# Eitech-Robotics_v10.net
KiCad netlist of a schematic drawn in EAGLE
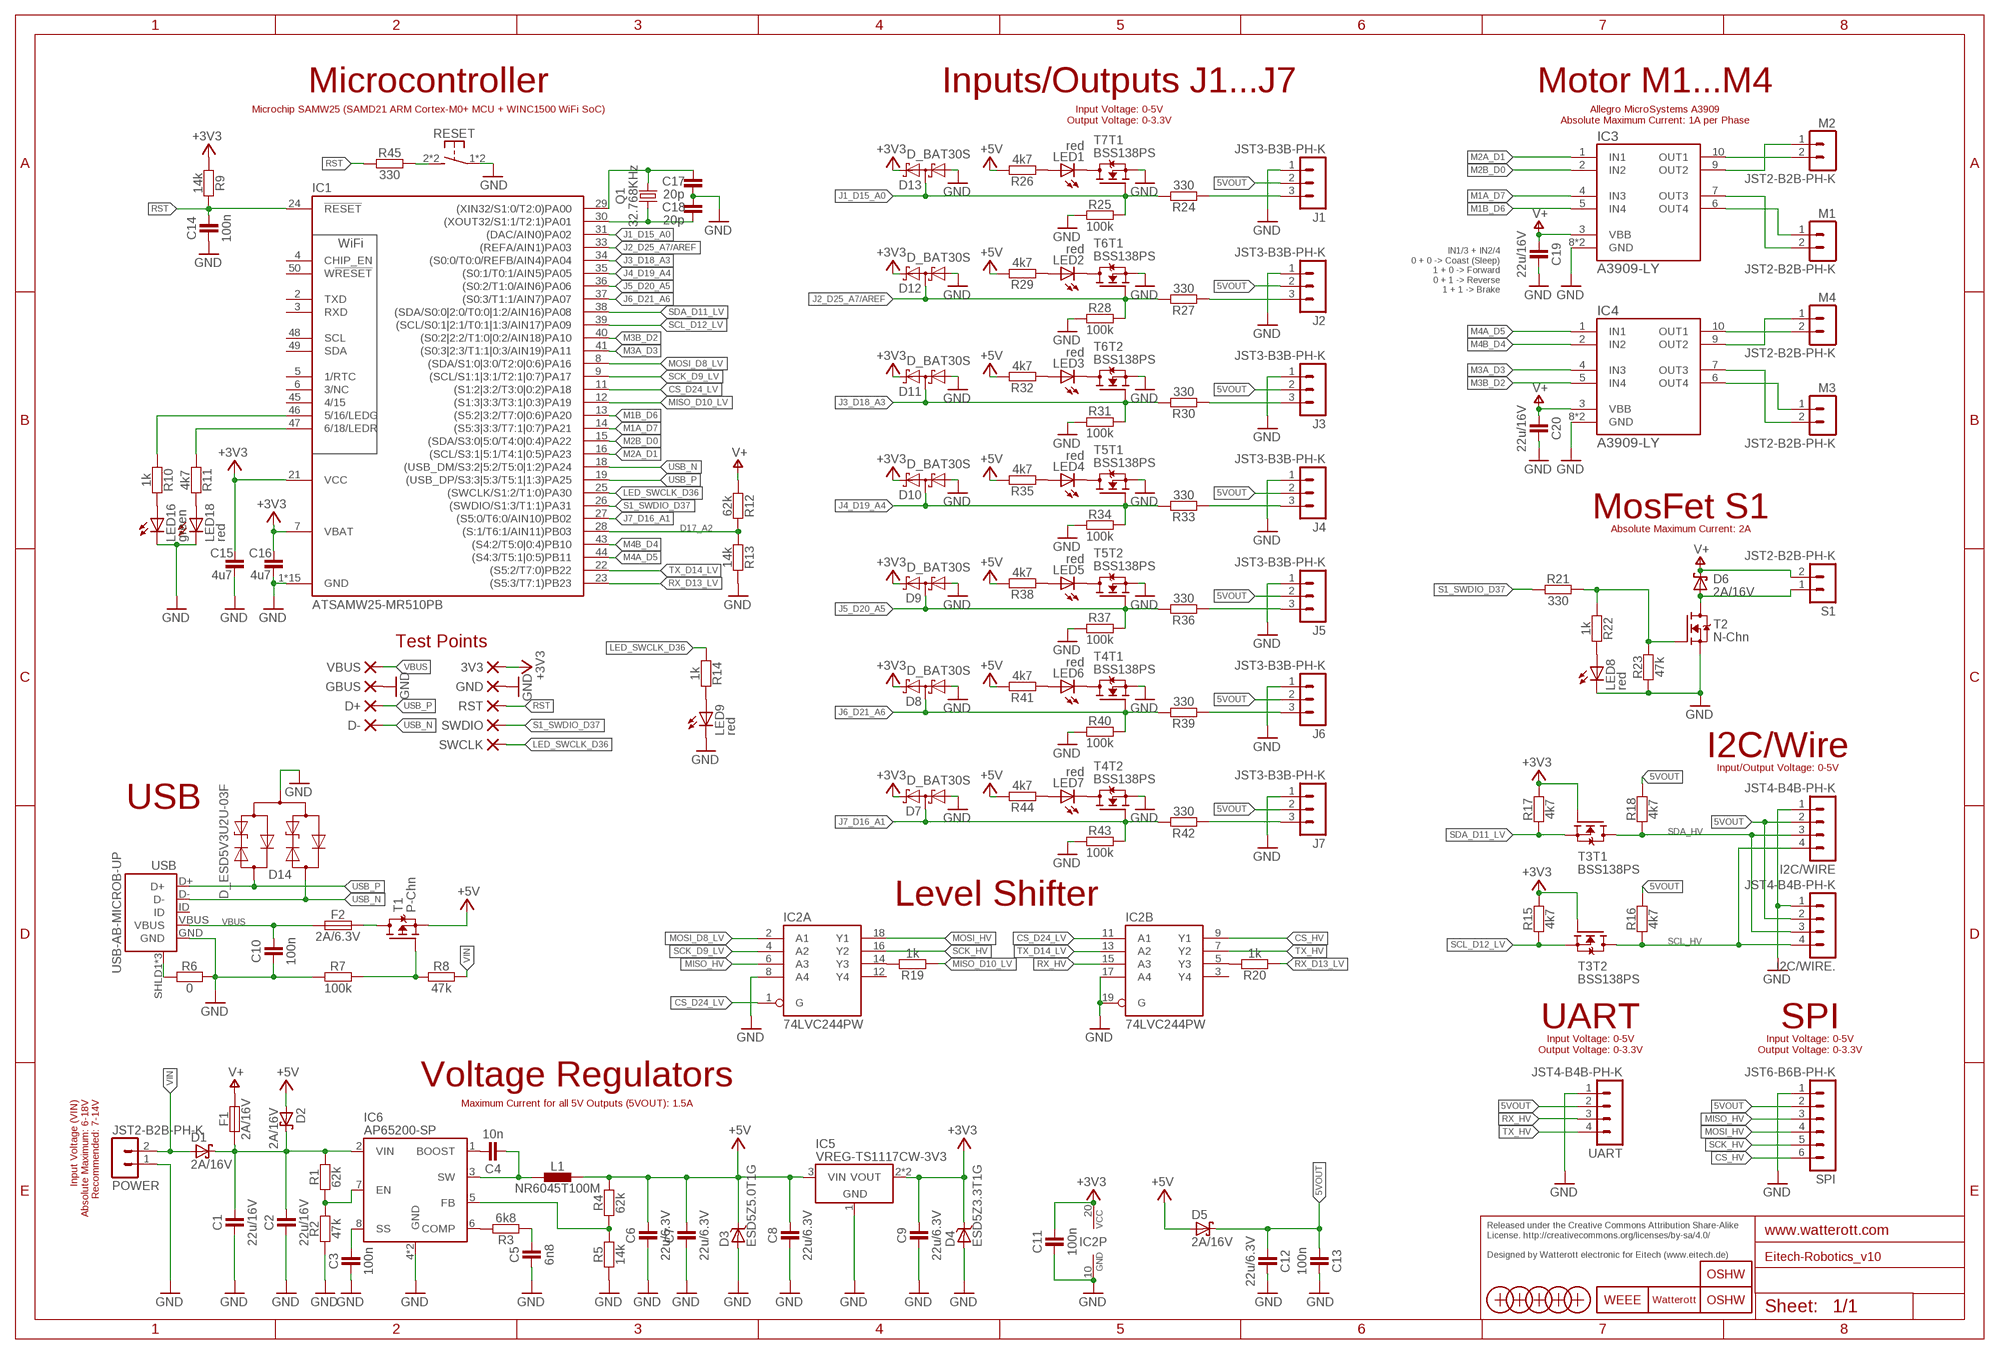
[diagram p0: schematic, sheet 1]

(export (version "E")
  (design (tool "Eeschema 10.0.6"))
  (components
    (comp (ref "3V3")
      (value "PAD-1.0_NC")
      (footprint "eagle-import:PAD-1.0_NC")
      (libsource (lib "eagle-import") (part "PAD-1.0_NC"))
    )
    (comp (ref "C1")
      (value "22u/16V")
      (footprint "eagle-import:C0805")
      (libsource (lib "eagle-import") (part "CAPACITOR-0805"))
    )
    (comp (ref "C2")
      (value "22u/16V")
      (footprint "eagle-import:C0805")
      (libsource (lib "eagle-import") (part "CAPACITOR-0805"))
    )
    (comp (ref "C3")
      (value "100n")
      (footprint "eagle-import:C0402")
      (libsource (lib "eagle-import") (part "CAPACITOR-0402"))
    )
    (comp (ref "C4")
      (value "10n")
      (footprint "eagle-import:C0402")
      (libsource (lib "eagle-import") (part "CAPACITOR-0402"))
    )
    (comp (ref "C5")
      (value "6n8")
      (footprint "eagle-import:C0402")
      (libsource (lib "eagle-import") (part "CAPACITOR-0402"))
    )
    (comp (ref "C6")
      (value "22u/6.3V")
      (footprint "eagle-import:C0805")
      (libsource (lib "eagle-import") (part "CAPACITOR-0805"))
    )
    (comp (ref "C7")
      (value "22u/6.3V")
      (footprint "eagle-import:C0805")
      (libsource (lib "eagle-import") (part "CAPACITOR-0805"))
    )
    (comp (ref "C8")
      (value "22u/6.3V")
      (footprint "eagle-import:C0805")
      (libsource (lib "eagle-import") (part "CAPACITOR-0805"))
    )
    (comp (ref "C9")
      (value "22u/6.3V")
      (footprint "eagle-import:C0805")
      (libsource (lib "eagle-import") (part "CAPACITOR-0805"))
    )
    (comp (ref "C10")
      (value "100n")
      (footprint "eagle-import:C0402")
      (libsource (lib "eagle-import") (part "CAPACITOR-0402"))
    )
    (comp (ref "C11")
      (value "100n")
      (footprint "eagle-import:C0402")
      (libsource (lib "eagle-import") (part "CAPACITOR-0402"))
    )
    (comp (ref "C12")
      (value "22u/6.3V")
      (footprint "eagle-import:C0805")
      (libsource (lib "eagle-import") (part "CAPACITOR-0805"))
    )
    (comp (ref "C13")
      (value "100n")
      (footprint "eagle-import:C0402")
      (libsource (lib "eagle-import") (part "CAPACITOR-0402"))
    )
    (comp (ref "C14")
      (value "100n")
      (footprint "eagle-import:C0402")
      (libsource (lib "eagle-import") (part "CAPACITOR-0402"))
    )
    (comp (ref "C15")
      (value "4u7")
      (footprint "eagle-import:C0603")
      (libsource (lib "eagle-import") (part "CAPACITOR-0603"))
    )
    (comp (ref "C16")
      (value "4u7")
      (footprint "eagle-import:C0603")
      (libsource (lib "eagle-import") (part "CAPACITOR-0603"))
    )
    (comp (ref "C17")
      (value "20p")
      (footprint "eagle-import:C0402")
      (libsource (lib "eagle-import") (part "CAPACITOR-0402"))
    )
    (comp (ref "C18")
      (value "20p")
      (footprint "eagle-import:C0402")
      (libsource (lib "eagle-import") (part "CAPACITOR-0402"))
    )
    (comp (ref "C19")
      (value "22u/16V")
      (footprint "eagle-import:C0805")
      (libsource (lib "eagle-import") (part "CAPACITOR-0805"))
    )
    (comp (ref "C20")
      (value "22u/16V")
      (footprint "eagle-import:C0805")
      (libsource (lib "eagle-import") (part "CAPACITOR-0805"))
    )
    (comp (ref "D+")
      (value "PAD-1.0_NC")
      (footprint "eagle-import:PAD-1.0_NC")
      (libsource (lib "eagle-import") (part "PAD-1.0_NC"))
    )
    (comp (ref "D-")
      (value "PAD-1.0_NC")
      (footprint "eagle-import:PAD-1.0_NC")
      (libsource (lib "eagle-import") (part "PAD-1.0_NC"))
    )
    (comp (ref "D1")
      (value "2A/16V")
      (footprint "eagle-import:SMA_DO214AC")
      (libsource (lib "eagle-import") (part "D_SCHOTTKY-SMA"))
    )
    (comp (ref "D2")
      (value "2A/16V")
      (footprint "eagle-import:SMA_DO214AC")
      (libsource (lib "eagle-import") (part "D_SCHOTTKY-SMA"))
    )
    (comp (ref "D3")
      (value "ESD5Z5.0T1G")
      (footprint "eagle-import:SOD523")
      (libsource (lib "eagle-import") (part "D_TVS-SOD523"))
    )
    (comp (ref "D4")
      (value "ESD5Z3.3T1G")
      (footprint "eagle-import:SOD523")
      (libsource (lib "eagle-import") (part "D_TVS-SOD523"))
    )
    (comp (ref "D5")
      (value "2A/16V")
      (footprint "eagle-import:SMA_DO214AC")
      (libsource (lib "eagle-import") (part "D_SCHOTTKY-SMA"))
    )
    (comp (ref "D6")
      (value "2A/16V")
      (footprint "eagle-import:SMA_DO214AC")
      (libsource (lib "eagle-import") (part "D_SCHOTTKY-SMA"))
    )
    (comp (ref "D7")
      (value "D_BAT30S")
      (footprint "eagle-import:SOT323")
      (libsource (lib "eagle-import") (part "D_BAT30S"))
    )
    (comp (ref "D8")
      (value "D_BAT30S")
      (footprint "eagle-import:SOT323")
      (libsource (lib "eagle-import") (part "D_BAT30S"))
    )
    (comp (ref "D9")
      (value "D_BAT30S")
      (footprint "eagle-import:SOT323")
      (libsource (lib "eagle-import") (part "D_BAT30S"))
    )
    (comp (ref "D10")
      (value "D_BAT30S")
      (footprint "eagle-import:SOT323")
      (libsource (lib "eagle-import") (part "D_BAT30S"))
    )
    (comp (ref "D11")
      (value "D_BAT30S")
      (footprint "eagle-import:SOT323")
      (libsource (lib "eagle-import") (part "D_BAT30S"))
    )
    (comp (ref "D12")
      (value "D_BAT30S")
      (footprint "eagle-import:SOT323")
      (libsource (lib "eagle-import") (part "D_BAT30S"))
    )
    (comp (ref "D13")
      (value "D_BAT30S")
      (footprint "eagle-import:SOT323")
      (libsource (lib "eagle-import") (part "D_BAT30S"))
    )
    (comp (ref "D14")
      (value "D_ESD5V3U2U-03F")
      (footprint "eagle-import:SOT723")
      (libsource (lib "eagle-import") (part "D_ESD5V3U2U-03F"))
    )
    (comp (ref "F1")
      (value "2A/16V")
      (footprint "eagle-import:C1812")
      (libsource (lib "eagle-import") (part "FUSE-1812"))
    )
    (comp (ref "F2")
      (value "2A/6.3V")
      (footprint "eagle-import:C1206")
      (libsource (lib "eagle-import") (part "FUSE-1206"))
    )
    (comp (ref "GBUS")
      (value "PAD-1.0_NC")
      (footprint "eagle-import:PAD-1.0_NC")
      (libsource (lib "eagle-import") (part "PAD-1.0_NC"))
    )
    (comp (ref "GND")
      (value "PAD-1.0_NC")
      (footprint "eagle-import:PAD-1.0_NC")
      (libsource (lib "eagle-import") (part "PAD-1.0_NC"))
    )
    (comp (ref "I2C/WIRE")
      (value "JST4-B4B-PH-K")
      (footprint "eagle-import:JST_B4B-PH-K")
      (libsource (lib "eagle-import") (part "JST4-B4B-PH-K"))
    )
    (comp (ref "I2C/WIRE.")
      (value "JST4-B4B-PH-K")
      (footprint "eagle-import:JST_B4B-PH-K")
      (libsource (lib "eagle-import") (part "JST4-B4B-PH-K"))
    )
    (comp (ref "IC1")
      (value "ATSAMW25-MR510PB")
      (footprint "eagle-import:ATSAMW25-MRX10")
      (libsource (lib "eagle-import") (part "ATSAMW25-MR510PB"))
    )
    (comp (ref "IC2")
      (value "74LVC244PW")
      (footprint "eagle-import:TSSOP20")
      (libsource (lib "eagle-import") (part "74244PWLVC"))
    )
    (comp (ref "IC3")
      (value "A3909-LY")
      (footprint "eagle-import:MSOP10-PAD")
      (libsource (lib "eagle-import") (part "A3909-LY"))
    )
    (comp (ref "IC4")
      (value "A3909-LY")
      (footprint "eagle-import:MSOP10-PAD")
      (libsource (lib "eagle-import") (part "A3909-LY"))
    )
    (comp (ref "IC5")
      (value "VREG-TS1117CW-3V3")
      (footprint "eagle-import:SOT223")
      (libsource (lib "eagle-import") (part "VREG-TS1117CW-3V3"))
    )
    (comp (ref "IC6")
      (value "AP65200-SP")
      (footprint "eagle-import:SO08-PAD")
      (libsource (lib "eagle-import") (part "AP65200-SP"))
    )
    (comp (ref "J1")
      (value "JST3-B3B-PH-K")
      (footprint "eagle-import:JST_B3B-PH-K")
      (libsource (lib "eagle-import") (part "JST3-B3B-PH-K"))
    )
    (comp (ref "J2")
      (value "JST3-B3B-PH-K")
      (footprint "eagle-import:JST_B3B-PH-K")
      (libsource (lib "eagle-import") (part "JST3-B3B-PH-K"))
    )
    (comp (ref "J3")
      (value "JST3-B3B-PH-K")
      (footprint "eagle-import:JST_B3B-PH-K")
      (libsource (lib "eagle-import") (part "JST3-B3B-PH-K"))
    )
    (comp (ref "J4")
      (value "JST3-B3B-PH-K")
      (footprint "eagle-import:JST_B3B-PH-K")
      (libsource (lib "eagle-import") (part "JST3-B3B-PH-K"))
    )
    (comp (ref "J5")
      (value "JST3-B3B-PH-K")
      (footprint "eagle-import:JST_B3B-PH-K")
      (libsource (lib "eagle-import") (part "JST3-B3B-PH-K"))
    )
    (comp (ref "J6")
      (value "JST3-B3B-PH-K")
      (footprint "eagle-import:JST_B3B-PH-K")
      (libsource (lib "eagle-import") (part "JST3-B3B-PH-K"))
    )
    (comp (ref "J7")
      (value "JST3-B3B-PH-K")
      (footprint "eagle-import:JST_B3B-PH-K")
      (libsource (lib "eagle-import") (part "JST3-B3B-PH-K"))
    )
    (comp (ref "L1")
      (value "NR6045T100M")
      (footprint "eagle-import:L_NR60XX")
      (libsource (lib "eagle-import") (part "INDUCTOR-NR60XX"))
    )
    (comp (ref "LED1")
      (value "red")
      (footprint "eagle-import:C0603")
      (libsource (lib "eagle-import") (part "LED-0603"))
    )
    (comp (ref "LED2")
      (value "red")
      (footprint "eagle-import:C0603")
      (libsource (lib "eagle-import") (part "LED-0603"))
    )
    (comp (ref "LED3")
      (value "red")
      (footprint "eagle-import:C0603")
      (libsource (lib "eagle-import") (part "LED-0603"))
    )
    (comp (ref "LED4")
      (value "red")
      (footprint "eagle-import:C0603")
      (libsource (lib "eagle-import") (part "LED-0603"))
    )
    (comp (ref "LED5")
      (value "red")
      (footprint "eagle-import:C0603")
      (libsource (lib "eagle-import") (part "LED-0603"))
    )
    (comp (ref "LED6")
      (value "red")
      (footprint "eagle-import:C0603")
      (libsource (lib "eagle-import") (part "LED-0603"))
    )
    (comp (ref "LED7")
      (value "red")
      (footprint "eagle-import:C0603")
      (libsource (lib "eagle-import") (part "LED-0603"))
    )
    (comp (ref "LED8")
      (value "red")
      (footprint "eagle-import:C0603")
      (libsource (lib "eagle-import") (part "LED-0603"))
    )
    (comp (ref "LED9")
      (value "red")
      (footprint "eagle-import:C0603")
      (libsource (lib "eagle-import") (part "LED-0603"))
    )
    (comp (ref "LED16")
      (value "green")
      (footprint "eagle-import:C0603")
      (libsource (lib "eagle-import") (part "LED-0603"))
    )
    (comp (ref "LED18")
      (value "red")
      (footprint "eagle-import:C0603")
      (libsource (lib "eagle-import") (part "LED-0603"))
    )
    (comp (ref "LOGO1")
      (value "OSHW_LOGOX0100")
      (footprint "eagle-import:OSHW_6X100")
      (libsource (lib "eagle-import") (part "OSHW_LOGOX0100"))
    )
    (comp (ref "LOGO2")
      (value "OSHW_LOGOX0150")
      (footprint "eagle-import:OSHW_6X150")
      (libsource (lib "eagle-import") (part "OSHW_LOGOX0150"))
    )
    (comp (ref "LOGO3")
      (value "LOGO-S_PLACE_S")
      (footprint "eagle-import:SPARK_TPLACE_S")
      (libsource (lib "eagle-import") (part "LOGO-S_PLACE_S"))
    )
    (comp (ref "LOGO4")
      (value "WEEE_LOGO-S")
      (footprint "eagle-import:WEEE_TPLAC_S")
      (libsource (lib "eagle-import") (part "WEEE_LOGO-S"))
    )
    (comp (ref "M1")
      (value "JST2-B2B-PH-K")
      (footprint "eagle-import:JST_B2B-PH-K")
      (libsource (lib "eagle-import") (part "JST2-B2B-PH-K"))
    )
    (comp (ref "M2")
      (value "JST2-B2B-PH-K")
      (footprint "eagle-import:JST_B2B-PH-K")
      (libsource (lib "eagle-import") (part "JST2-B2B-PH-K"))
    )
    (comp (ref "M3")
      (value "JST2-B2B-PH-K")
      (footprint "eagle-import:JST_B2B-PH-K")
      (libsource (lib "eagle-import") (part "JST2-B2B-PH-K"))
    )
    (comp (ref "M4")
      (value "JST2-B2B-PH-K")
      (footprint "eagle-import:JST_B2B-PH-K")
      (libsource (lib "eagle-import") (part "JST2-B2B-PH-K"))
    )
    (comp (ref "POWER")
      (value "JST2-B2B-PH-K")
      (footprint "eagle-import:JST_B2B-PH-K")
      (libsource (lib "eagle-import") (part "JST2-B2B-PH-K"))
    )
    (comp (ref "Q1")
      (value "32.768KHz")
      (footprint "eagle-import:CRYSTAL_ZM315")
      (libsource (lib "eagle-import") (part "CRYSTAL-ZM315"))
    )
    (comp (ref "R1")
      (value "62k")
      (footprint "eagle-import:C0402")
      (libsource (lib "eagle-import") (part "RESISTOR-0402"))
    )
    (comp (ref "R2")
      (value "47k")
      (footprint "eagle-import:C0402")
      (libsource (lib "eagle-import") (part "RESISTOR-0402"))
    )
    (comp (ref "R3")
      (value "6k8")
      (footprint "eagle-import:C0402")
      (libsource (lib "eagle-import") (part "RESISTOR-0402"))
    )
    (comp (ref "R4")
      (value "62k")
      (footprint "eagle-import:C0402")
      (libsource (lib "eagle-import") (part "RESISTOR-0402"))
    )
    (comp (ref "R5")
      (value "14k")
      (footprint "eagle-import:C0402")
      (libsource (lib "eagle-import") (part "RESISTOR-0402"))
    )
    (comp (ref "R6")
      (value "0")
      (footprint "eagle-import:C0402")
      (libsource (lib "eagle-import") (part "RESISTOR-0402"))
    )
    (comp (ref "R7")
      (value "100k")
      (footprint "eagle-import:C0402")
      (libsource (lib "eagle-import") (part "RESISTOR-0402"))
    )
    (comp (ref "R8")
      (value "47k")
      (footprint "eagle-import:C0402")
      (libsource (lib "eagle-import") (part "RESISTOR-0402"))
    )
    (comp (ref "R9")
      (value "14k")
      (footprint "eagle-import:C0402")
      (libsource (lib "eagle-import") (part "RESISTOR-0402"))
    )
    (comp (ref "R10")
      (value "1k")
      (footprint "eagle-import:C0402")
      (libsource (lib "eagle-import") (part "RESISTOR-0402"))
    )
    (comp (ref "R11")
      (value "4k7")
      (footprint "eagle-import:C0402")
      (libsource (lib "eagle-import") (part "RESISTOR-0402"))
    )
    (comp (ref "R12")
      (value "62k")
      (footprint "eagle-import:C0402")
      (libsource (lib "eagle-import") (part "RESISTOR-0402"))
    )
    (comp (ref "R13")
      (value "14k")
      (footprint "eagle-import:C0402")
      (libsource (lib "eagle-import") (part "RESISTOR-0402"))
    )
    (comp (ref "R14")
      (value "1k")
      (footprint "eagle-import:C0402")
      (libsource (lib "eagle-import") (part "RESISTOR-0402"))
    )
    (comp (ref "R15")
      (value "4k7")
      (footprint "eagle-import:C0402")
      (libsource (lib "eagle-import") (part "RESISTOR-0402"))
    )
    (comp (ref "R16")
      (value "4k7")
      (footprint "eagle-import:C0402")
      (libsource (lib "eagle-import") (part "RESISTOR-0402"))
    )
    (comp (ref "R17")
      (value "4k7")
      (footprint "eagle-import:C0402")
      (libsource (lib "eagle-import") (part "RESISTOR-0402"))
    )
    (comp (ref "R18")
      (value "4k7")
      (footprint "eagle-import:C0402")
      (libsource (lib "eagle-import") (part "RESISTOR-0402"))
    )
    (comp (ref "R19")
      (value "1k")
      (footprint "eagle-import:C0402")
      (libsource (lib "eagle-import") (part "RESISTOR-0402"))
    )
    (comp (ref "R20")
      (value "1k")
      (footprint "eagle-import:C0402")
      (libsource (lib "eagle-import") (part "RESISTOR-0402"))
    )
    (comp (ref "R21")
      (value "330")
      (footprint "eagle-import:C0402")
      (libsource (lib "eagle-import") (part "RESISTOR-0402"))
    )
    (comp (ref "R22")
      (value "1k")
      (footprint "eagle-import:C0402")
      (libsource (lib "eagle-import") (part "RESISTOR-0402"))
    )
    (comp (ref "R23")
      (value "47k")
      (footprint "eagle-import:C0402")
      (libsource (lib "eagle-import") (part "RESISTOR-0402"))
    )
    (comp (ref "R24")
      (value "330")
      (footprint "eagle-import:C0402")
      (libsource (lib "eagle-import") (part "RESISTOR-0402"))
    )
    (comp (ref "R25")
      (value "100k")
      (footprint "eagle-import:C0402")
      (libsource (lib "eagle-import") (part "RESISTOR-0402"))
    )
    (comp (ref "R26")
      (value "4k7")
      (footprint "eagle-import:C0402")
      (libsource (lib "eagle-import") (part "RESISTOR-0402"))
    )
    (comp (ref "R27")
      (value "330")
      (footprint "eagle-import:C0402")
      (libsource (lib "eagle-import") (part "RESISTOR-0402"))
    )
    (comp (ref "R28")
      (value "100k")
      (footprint "eagle-import:C0402")
      (libsource (lib "eagle-import") (part "RESISTOR-0402"))
    )
    (comp (ref "R29")
      (value "4k7")
      (footprint "eagle-import:C0402")
      (libsource (lib "eagle-import") (part "RESISTOR-0402"))
    )
    (comp (ref "R30")
      (value "330")
      (footprint "eagle-import:C0402")
      (libsource (lib "eagle-import") (part "RESISTOR-0402"))
    )
    (comp (ref "R31")
      (value "100k")
      (footprint "eagle-import:C0402")
      (libsource (lib "eagle-import") (part "RESISTOR-0402"))
    )
    (comp (ref "R32")
      (value "4k7")
      (footprint "eagle-import:C0402")
      (libsource (lib "eagle-import") (part "RESISTOR-0402"))
    )
    (comp (ref "R33")
      (value "330")
      (footprint "eagle-import:C0402")
      (libsource (lib "eagle-import") (part "RESISTOR-0402"))
    )
    (comp (ref "R34")
      (value "100k")
      (footprint "eagle-import:C0402")
      (libsource (lib "eagle-import") (part "RESISTOR-0402"))
    )
    (comp (ref "R35")
      (value "4k7")
      (footprint "eagle-import:C0402")
      (libsource (lib "eagle-import") (part "RESISTOR-0402"))
    )
    (comp (ref "R36")
      (value "330")
      (footprint "eagle-import:C0402")
      (libsource (lib "eagle-import") (part "RESISTOR-0402"))
    )
    (comp (ref "R37")
      (value "100k")
      (footprint "eagle-import:C0402")
      (libsource (lib "eagle-import") (part "RESISTOR-0402"))
    )
    (comp (ref "R38")
      (value "4k7")
      (footprint "eagle-import:C0402")
      (libsource (lib "eagle-import") (part "RESISTOR-0402"))
    )
    (comp (ref "R39")
      (value "330")
      (footprint "eagle-import:C0402")
      (libsource (lib "eagle-import") (part "RESISTOR-0402"))
    )
    (comp (ref "R40")
      (value "100k")
      (footprint "eagle-import:C0402")
      (libsource (lib "eagle-import") (part "RESISTOR-0402"))
    )
    (comp (ref "R41")
      (value "4k7")
      (footprint "eagle-import:C0402")
      (libsource (lib "eagle-import") (part "RESISTOR-0402"))
    )
    (comp (ref "R42")
      (value "330")
      (footprint "eagle-import:C0402")
      (libsource (lib "eagle-import") (part "RESISTOR-0402"))
    )
    (comp (ref "R43")
      (value "100k")
      (footprint "eagle-import:C0402")
      (libsource (lib "eagle-import") (part "RESISTOR-0402"))
    )
    (comp (ref "R44")
      (value "4k7")
      (footprint "eagle-import:C0402")
      (libsource (lib "eagle-import") (part "RESISTOR-0402"))
    )
    (comp (ref "R45")
      (value "330")
      (footprint "eagle-import:C0402")
      (libsource (lib "eagle-import") (part "RESISTOR-0402"))
    )
    (comp (ref "RESET")
      (value "SW-TACTILE-TL3305C")
      (footprint "eagle-import:TL3305")
      (fields (field (name "MPN") "TL3305C"))
      (libsource (lib "eagle-import") (part "SW-TACTILE-TL3305"))
    )
    (comp (ref "RST")
      (value "PAD-1.0_NC")
      (footprint "eagle-import:PAD-1.0_NC")
      (libsource (lib "eagle-import") (part "PAD-1.0_NC"))
    )
    (comp (ref "S1")
      (value "JST2-B2B-PH-K")
      (footprint "eagle-import:JST_B2B-PH-K")
      (libsource (lib "eagle-import") (part "JST2-B2B-PH-K"))
    )
    (comp (ref "SPI")
      (value "JST6-B6B-PH-K")
      (footprint "eagle-import:JST_B6B-PH-K")
      (libsource (lib "eagle-import") (part "JST6-B6B-PH-K"))
    )
    (comp (ref "SWCLK")
      (value "PAD-1.0_NC")
      (footprint "eagle-import:PAD-1.0_NC")
      (libsource (lib "eagle-import") (part "PAD-1.0_NC"))
    )
    (comp (ref "SWDIO")
      (value "PAD-1.0_NC")
      (footprint "eagle-import:PAD-1.0_NC")
      (libsource (lib "eagle-import") (part "PAD-1.0_NC"))
    )
    (comp (ref "T1")
      (value "P-Chn")
      (footprint "eagle-import:SOT23")
      (libsource (lib "eagle-import") (part "MOSFET-P-SOT23"))
    )
    (comp (ref "T2")
      (value "N-Chn")
      (footprint "eagle-import:SOT23")
      (libsource (lib "eagle-import") (part "MOSFET-N-SOT23"))
    )
    (comp (ref "T3")
      (value "BSS138PS")
      (footprint "eagle-import:SOT363")
      (libsource (lib "eagle-import") (part "BSS138PS"))
    )
    (comp (ref "T4")
      (value "BSS138PS")
      (footprint "eagle-import:SOT363")
      (libsource (lib "eagle-import") (part "BSS138PS"))
    )
    (comp (ref "T5")
      (value "BSS138PS")
      (footprint "eagle-import:SOT363")
      (libsource (lib "eagle-import") (part "BSS138PS"))
    )
    (comp (ref "T6")
      (value "BSS138PS")
      (footprint "eagle-import:SOT363")
      (libsource (lib "eagle-import") (part "BSS138PS"))
    )
    (comp (ref "T7")
      (value "BSS138PS")
      (footprint "eagle-import:SOT363")
      (libsource (lib "eagle-import") (part "BSS138PS"))
    )
    (comp (ref "UART")
      (value "JST4-B4B-PH-K")
      (footprint "eagle-import:JST_B4B-PH-K")
      (libsource (lib "eagle-import") (part "JST4-B4B-PH-K"))
    )
    (comp (ref "USB")
      (value "USB-AB-MICROB-UP")
      (footprint "eagle-import:USB-MICROB-1051330011")
      (libsource (lib "eagle-import") (part "USB-AB-MICROB-UP"))
    )
    (comp (ref "VBUS")
      (value "PAD-1.0_NC")
      (footprint "eagle-import:PAD-1.0_NC")
      (libsource (lib "eagle-import") (part "PAD-1.0_NC"))
    )
    (comp (ref "X1")
      (value "PASSER-07")
      (footprint "eagle-import:PASSER_07MM")
      (libsource (lib "eagle-import") (part "PASSER-07"))
    )
    (comp (ref "X2")
      (value "PASSER-07")
      (footprint "eagle-import:PASSER_07MM")
      (libsource (lib "eagle-import") (part "PASSER-07"))
    )
    (comp (ref "X3")
      (value "PASSER-07")
      (footprint "eagle-import:PASSER_07MM")
      (libsource (lib "eagle-import") (part "PASSER-07"))
    )
    (comp (ref "X4")
      (value "PASSER-07")
      (footprint "eagle-import:PASSER_07MM")
      (libsource (lib "eagle-import") (part "PASSER-07"))
    )
    (comp (ref "X5")
      (value "PASSER-04")
      (footprint "eagle-import:PASSER_04MM")
      (libsource (lib "eagle-import") (part "PASSER-04"))
    )
  )
  (nets
    (net (code "1") (name "+3V3") (class "Default")
      (node (ref "3V3") (pin "1") (pinfunction "P_1") (pintype "passive"))
      (node (ref "C11") (pin "2") (pinfunction "2_2") (pintype "passive"))
      (node (ref "C15") (pin "2") (pinfunction "2_2") (pintype "passive"))
      (node (ref "C16") (pin "2") (pinfunction "2_2") (pintype "passive"))
      (node (ref "C9") (pin "2") (pinfunction "2_2") (pintype "passive"))
      (node (ref "D10") (pin "2") (pinfunction "C_2") (pintype "passive"))
      (node (ref "D11") (pin "2") (pinfunction "C_2") (pintype "passive"))
      (node (ref "D12") (pin "2") (pinfunction "C_2") (pintype "passive"))
      (node (ref "D13") (pin "2") (pinfunction "C_2") (pintype "passive"))
      (node (ref "D4") (pin "C") (pinfunction "C_C") (pintype "passive"))
      (node (ref "D7") (pin "2") (pinfunction "C_2") (pintype "passive"))
      (node (ref "D8") (pin "2") (pinfunction "C_2") (pintype "passive"))
      (node (ref "D9") (pin "2") (pinfunction "C_2") (pintype "passive"))
      (node (ref "IC1") (pin "21") (pinfunction "VCC_21") (pintype "power_in"))
      (node (ref "IC1") (pin "7") (pinfunction "VBAT_7") (pintype "power_in"))
      (node (ref "IC2") (pin "20") (pinfunction "VCC_20") (pintype "power_in"))
      (node (ref "IC5") (pin "2") (pinfunction "VOUT_2") (pintype "power_in"))
      (node (ref "IC5") (pin "4") (pinfunction "VOUT_4") (pintype "power_in"))
      (node (ref "R15") (pin "2") (pinfunction "2_2") (pintype "passive"))
      (node (ref "R17") (pin "2") (pinfunction "2_2") (pintype "passive"))
      (node (ref "R9") (pin "1") (pinfunction "1_1") (pintype "passive"))
      (node (ref "T3") (pin "2") (pinfunction "G_2") (pintype "passive"))
      (node (ref "T3") (pin "5") (pinfunction "G_5") (pintype "passive"))
    )
    (net (code "2") (name "+5V") (class "Default")
      (node (ref "C6") (pin "2") (pinfunction "2_2") (pintype "passive"))
      (node (ref "C7") (pin "2") (pinfunction "2_2") (pintype "passive"))
      (node (ref "C8") (pin "2") (pinfunction "2_2") (pintype "passive"))
      (node (ref "D2") (pin "A") (pinfunction "A_A") (pintype "passive"))
      (node (ref "D3") (pin "C") (pinfunction "C_C") (pintype "passive"))
      (node (ref "D5") (pin "A") (pinfunction "A_A") (pintype "passive"))
      (node (ref "IC5") (pin "3") (pinfunction "VIN_3") (pintype "power_in"))
      (node (ref "L1") (pin "2") (pinfunction "2_2") (pintype "passive"))
      (node (ref "R26") (pin "2") (pinfunction "2_2") (pintype "passive"))
      (node (ref "R29") (pin "2") (pinfunction "2_2") (pintype "passive"))
      (node (ref "R32") (pin "2") (pinfunction "2_2") (pintype "passive"))
      (node (ref "R35") (pin "2") (pinfunction "2_2") (pintype "passive"))
      (node (ref "R38") (pin "2") (pinfunction "2_2") (pintype "passive"))
      (node (ref "R4") (pin "2") (pinfunction "2_2") (pintype "passive"))
      (node (ref "R41") (pin "2") (pinfunction "2_2") (pintype "passive"))
      (node (ref "R44") (pin "2") (pinfunction "2_2") (pintype "passive"))
      (node (ref "T1") (pin "2") (pinfunction "S_2") (pintype "passive"))
    )
    (net (code "3") (name "/D17_A2") (class "Default")
      (node (ref "IC1") (pin "28") (pinfunction "(S:1/T6:1/AIN11)PB03_28") (pintype "bidirectional"))
      (node (ref "R12") (pin "2") (pinfunction "2_2") (pintype "passive"))
      (node (ref "R13") (pin "1") (pinfunction "1_1") (pintype "passive"))
    )
    (net (code "4") (name "/SCL_HV") (class "Default")
      (node (ref "I2C/WIRE") (pin "4") (pinfunction "4_4") (pintype "passive"))
      (node (ref "I2C/WIRE.") (pin "4") (pinfunction "4_4") (pintype "passive"))
      (node (ref "R16") (pin "1") (pinfunction "1_1") (pintype "passive"))
      (node (ref "T3") (pin "3") (pinfunction "D_3") (pintype "passive"))
    )
    (net (code "5") (name "/SDA_HV") (class "Default")
      (node (ref "I2C/WIRE") (pin "3") (pinfunction "3_3") (pintype "passive"))
      (node (ref "I2C/WIRE.") (pin "3") (pinfunction "3_3") (pintype "passive"))
      (node (ref "R18") (pin "1") (pinfunction "1_1") (pintype "passive"))
      (node (ref "T3") (pin "6") (pinfunction "D_6") (pintype "passive"))
    )
    (net (code "6") (name "5VOUT") (class "Default")
      (node (ref "C12") (pin "2") (pinfunction "2_2") (pintype "passive"))
      (node (ref "C13") (pin "2") (pinfunction "2_2") (pintype "passive"))
      (node (ref "D5") (pin "C") (pinfunction "C_C") (pintype "passive"))
      (node (ref "I2C/WIRE") (pin "2") (pinfunction "2_2") (pintype "passive"))
      (node (ref "I2C/WIRE.") (pin "2") (pinfunction "2_2") (pintype "passive"))
      (node (ref "J1") (pin "2") (pinfunction "2_2") (pintype "passive"))
      (node (ref "J2") (pin "2") (pinfunction "2_2") (pintype "passive"))
      (node (ref "J3") (pin "2") (pinfunction "2_2") (pintype "passive"))
      (node (ref "J4") (pin "2") (pinfunction "2_2") (pintype "passive"))
      (node (ref "J5") (pin "2") (pinfunction "2_2") (pintype "passive"))
      (node (ref "J6") (pin "2") (pinfunction "2_2") (pintype "passive"))
      (node (ref "J7") (pin "2") (pinfunction "2_2") (pintype "passive"))
      (node (ref "R16") (pin "2") (pinfunction "2_2") (pintype "passive"))
      (node (ref "R18") (pin "2") (pinfunction "2_2") (pintype "passive"))
      (node (ref "SPI") (pin "2") (pinfunction "2_2") (pintype "passive"))
      (node (ref "UART") (pin "2") (pinfunction "2_2") (pintype "passive"))
    )
    (net (code "7") (name "CS_D24_LV") (class "Default")
      (node (ref "IC1") (pin "11") (pinfunction "(S1:2|3:2/T3:0|0:2)PA18_11") (pintype "bidirectional"))
      (node (ref "IC2") (pin "1") (pinfunction "G_1") (pintype "input"))
      (node (ref "IC2") (pin "11") (pinfunction "A1_11") (pintype "input"))
    )
    (net (code "8") (name "CS_HV") (class "Default")
      (node (ref "IC2") (pin "9") (pinfunction "Y1_9") (pintype "tri_state"))
      (node (ref "SPI") (pin "6") (pinfunction "6_6") (pintype "passive"))
    )
    (net (code "9") (name "GND") (class "Default")
      (node (ref "C1") (pin "1") (pinfunction "1_1") (pintype "passive"))
      (node (ref "C10") (pin "1") (pinfunction "1_1") (pintype "passive"))
      (node (ref "C11") (pin "1") (pinfunction "1_1") (pintype "passive"))
      (node (ref "C12") (pin "1") (pinfunction "1_1") (pintype "passive"))
      (node (ref "C13") (pin "1") (pinfunction "1_1") (pintype "passive"))
      (node (ref "C14") (pin "1") (pinfunction "1_1") (pintype "passive"))
      (node (ref "C15") (pin "1") (pinfunction "1_1") (pintype "passive"))
      (node (ref "C16") (pin "1") (pinfunction "1_1") (pintype "passive"))
      (node (ref "C17") (pin "2") (pinfunction "2_2") (pintype "passive"))
      (node (ref "C18") (pin "2") (pinfunction "2_2") (pintype "passive"))
      (node (ref "C19") (pin "2") (pinfunction "2_2") (pintype "passive"))
      (node (ref "C2") (pin "1") (pinfunction "1_1") (pintype "passive"))
      (node (ref "C20") (pin "2") (pinfunction "2_2") (pintype "passive"))
      (node (ref "C3") (pin "1") (pinfunction "1_1") (pintype "passive"))
      (node (ref "C5") (pin "1") (pinfunction "1_1") (pintype "passive"))
      (node (ref "C6") (pin "1") (pinfunction "1_1") (pintype "passive"))
      (node (ref "C7") (pin "1") (pinfunction "1_1") (pintype "passive"))
      (node (ref "C8") (pin "1") (pinfunction "1_1") (pintype "passive"))
      (node (ref "C9") (pin "1") (pinfunction "1_1") (pintype "passive"))
      (node (ref "D10") (pin "1") (pinfunction "A_1") (pintype "passive"))
      (node (ref "D11") (pin "1") (pinfunction "A_1") (pintype "passive"))
      (node (ref "D12") (pin "1") (pinfunction "A_1") (pintype "passive"))
      (node (ref "D13") (pin "1") (pinfunction "A_1") (pintype "passive"))
      (node (ref "D14") (pin "3") (pinfunction "A_3") (pintype "passive"))
      (node (ref "D3") (pin "A") (pinfunction "A_A") (pintype "passive"))
      (node (ref "D4") (pin "A") (pinfunction "A_A") (pintype "passive"))
      (node (ref "D7") (pin "1") (pinfunction "A_1") (pintype "passive"))
      (node (ref "D8") (pin "1") (pinfunction "A_1") (pintype "passive"))
      (node (ref "D9") (pin "1") (pinfunction "A_1") (pintype "passive"))
      (node (ref "GBUS") (pin "1") (pinfunction "P_1") (pintype "passive"))
      (node (ref "GND") (pin "1") (pinfunction "P_1") (pintype "passive"))
      (node (ref "I2C/WIRE") (pin "1") (pinfunction "1_1") (pintype "passive"))
      (node (ref "I2C/WIRE.") (pin "1") (pinfunction "1_1") (pintype "passive"))
      (node (ref "IC1") (pin "1") (pinfunction "GND_1") (pintype "power_in"))
      (node (ref "IC1") (pin "10") (pinfunction "GND_10") (pintype "power_in"))
      (node (ref "IC1") (pin "17") (pinfunction "GND_17") (pintype "power_in"))
      (node (ref "IC1") (pin "20") (pinfunction "GND_20") (pintype "power_in"))
      (node (ref "IC1") (pin "32") (pinfunction "GND_32") (pintype "power_in"))
      (node (ref "IC1") (pin "42") (pinfunction "GND_42") (pintype "power_in"))
      (node (ref "IC1") (pin "51") (pinfunction "GND_51") (pintype "power_in"))
      (node (ref "IC1") (pin "GND@1") (pinfunction "GND_GND@1") (pintype "power_in"))
      (node (ref "IC1") (pin "GND@2") (pinfunction "GND_GND@2") (pintype "power_in"))
      (node (ref "IC1") (pin "GND@3") (pinfunction "GND_GND@3") (pintype "power_in"))
      (node (ref "IC1") (pin "GND@4") (pinfunction "GND_GND@4") (pintype "power_in"))
      (node (ref "IC1") (pin "GND@5") (pinfunction "GND_GND@5") (pintype "power_in"))
      (node (ref "IC1") (pin "GND@6") (pinfunction "GND_GND@6") (pintype "power_in"))
      (node (ref "IC1") (pin "GND@7") (pinfunction "GND_GND@7") (pintype "power_in"))
      (node (ref "IC1") (pin "GND@8") (pinfunction "GND_GND@8") (pintype "power_in"))
      (node (ref "IC2") (pin "10") (pinfunction "GND_10") (pintype "power_in"))
      (node (ref "IC2") (pin "17") (pinfunction "A4_17") (pintype "input"))
      (node (ref "IC2") (pin "19") (pinfunction "G_19") (pintype "input"))
      (node (ref "IC2") (pin "8") (pinfunction "A4_8") (pintype "input"))
      (node (ref "IC3") (pin "8") (pinfunction "GND_8") (pintype "power_in"))
      (node (ref "IC3") (pin "TP") (pinfunction "GND_TP") (pintype "power_in"))
      (node (ref "IC4") (pin "8") (pinfunction "GND_8") (pintype "power_in"))
      (node (ref "IC4") (pin "TP") (pinfunction "GND_TP") (pintype "power_in"))
      (node (ref "IC5") (pin "1") (pinfunction "GND_1") (pintype "power_in"))
      (node (ref "IC6") (pin "4") (pinfunction "GND_4") (pintype "power_in"))
      (node (ref "IC6") (pin "TP") (pinfunction "GND_TP") (pintype "power_in"))
      (node (ref "J1") (pin "1") (pinfunction "1_1") (pintype "passive"))
      (node (ref "J2") (pin "1") (pinfunction "1_1") (pintype "passive"))
      (node (ref "J3") (pin "1") (pinfunction "1_1") (pintype "passive"))
      (node (ref "J4") (pin "1") (pinfunction "1_1") (pintype "passive"))
      (node (ref "J5") (pin "1") (pinfunction "1_1") (pintype "passive"))
      (node (ref "J6") (pin "1") (pinfunction "1_1") (pintype "passive"))
      (node (ref "J7") (pin "1") (pinfunction "1_1") (pintype "passive"))
      (node (ref "LED16") (pin "C") (pinfunction "C_C") (pintype "passive"))
      (node (ref "LED18") (pin "C") (pinfunction "C_C") (pintype "passive"))
      (node (ref "LED8") (pin "C") (pinfunction "C_C") (pintype "passive"))
      (node (ref "LED9") (pin "C") (pinfunction "C_C") (pintype "passive"))
      (node (ref "POWER") (pin "1") (pinfunction "2_1") (pintype "passive"))
      (node (ref "R13") (pin "2") (pinfunction "2_2") (pintype "passive"))
      (node (ref "R2") (pin "1") (pinfunction "1_1") (pintype "passive"))
      (node (ref "R23") (pin "1") (pinfunction "1_1") (pintype "passive"))
      (node (ref "R25") (pin "1") (pinfunction "1_1") (pintype "passive"))
      (node (ref "R28") (pin "1") (pinfunction "1_1") (pintype "passive"))
      (node (ref "R31") (pin "1") (pinfunction "1_1") (pintype "passive"))
      (node (ref "R34") (pin "1") (pinfunction "1_1") (pintype "passive"))
      (node (ref "R37") (pin "1") (pinfunction "1_1") (pintype "passive"))
      (node (ref "R40") (pin "1") (pinfunction "1_1") (pintype "passive"))
      (node (ref "R43") (pin "1") (pinfunction "1_1") (pintype "passive"))
      (node (ref "R5") (pin "1") (pinfunction "1_1") (pintype "passive"))
      (node (ref "R6") (pin "1") (pinfunction "1_1") (pintype "passive"))
      (node (ref "R7") (pin "1") (pinfunction "1_1") (pintype "passive"))
      (node (ref "RESET") (pin "1") (pinfunction "P1_1") (pintype "passive"))
      (node (ref "RESET") (pin "4") (pinfunction "P1_4") (pintype "passive"))
      (node (ref "SPI") (pin "1") (pinfunction "1_1") (pintype "passive"))
      (node (ref "T2") (pin "2") (pinfunction "S_2") (pintype "passive"))
      (node (ref "T4") (pin "1") (pinfunction "S_1") (pintype "passive"))
      (node (ref "T4") (pin "4") (pinfunction "S_4") (pintype "passive"))
      (node (ref "T5") (pin "1") (pinfunction "S_1") (pintype "passive"))
      (node (ref "T5") (pin "4") (pinfunction "S_4") (pintype "passive"))
      (node (ref "T6") (pin "1") (pinfunction "S_1") (pintype "passive"))
      (node (ref "T6") (pin "4") (pinfunction "S_4") (pintype "passive"))
      (node (ref "T7") (pin "1") (pinfunction "S_1") (pintype "passive"))
      (node (ref "UART") (pin "1") (pinfunction "1_1") (pintype "passive"))
      (node (ref "USB") (pin "GND") (pinfunction "GND_GND") (pintype "power_in"))
    )
    (net (code "10") (name "J1_D15_A0") (class "Default")
      (node (ref "D13") (pin "3") (pinfunction "CA_3") (pintype "passive"))
      (node (ref "IC1") (pin "31") (pinfunction "(DAC/AIN0)PA02_31") (pintype "bidirectional"))
      (node (ref "R24") (pin "2") (pinfunction "2_2") (pintype "passive"))
      (node (ref "R25") (pin "2") (pinfunction "2_2") (pintype "passive"))
      (node (ref "T7") (pin "2") (pinfunction "G_2") (pintype "passive"))
    )
    (net (code "11") (name "J2_D25_A7{slash}AREF") (class "Default")
      (node (ref "D12") (pin "3") (pinfunction "CA_3") (pintype "passive"))
      (node (ref "IC1") (pin "33") (pinfunction "(REFA/AIN1)PA03_33") (pintype "bidirectional"))
      (node (ref "R27") (pin "2") (pinfunction "2_2") (pintype "passive"))
      (node (ref "R28") (pin "2") (pinfunction "2_2") (pintype "passive"))
      (node (ref "T6") (pin "2") (pinfunction "G_2") (pintype "passive"))
    )
    (net (code "12") (name "J3_D18_A3") (class "Default")
      (node (ref "D11") (pin "3") (pinfunction "CA_3") (pintype "passive"))
      (node (ref "IC1") (pin "34") (pinfunction "(S0:0/T0:0/REFB/AIN4)PA04_34") (pintype "bidirectional"))
      (node (ref "R30") (pin "2") (pinfunction "2_2") (pintype "passive"))
      (node (ref "R31") (pin "2") (pinfunction "2_2") (pintype "passive"))
      (node (ref "T6") (pin "5") (pinfunction "G_5") (pintype "passive"))
    )
    (net (code "13") (name "J4_D19_A4") (class "Default")
      (node (ref "D10") (pin "3") (pinfunction "CA_3") (pintype "passive"))
      (node (ref "IC1") (pin "35") (pinfunction "(S0:1/T0:1/AIN5)PA05_35") (pintype "bidirectional"))
      (node (ref "R33") (pin "2") (pinfunction "2_2") (pintype "passive"))
      (node (ref "R34") (pin "2") (pinfunction "2_2") (pintype "passive"))
      (node (ref "T5") (pin "2") (pinfunction "G_2") (pintype "passive"))
    )
    (net (code "14") (name "J5_D20_A5") (class "Default")
      (node (ref "D9") (pin "3") (pinfunction "CA_3") (pintype "passive"))
      (node (ref "IC1") (pin "36") (pinfunction "(S0:2/T1:0/AIN6)PA06_36") (pintype "bidirectional"))
      (node (ref "R36") (pin "2") (pinfunction "2_2") (pintype "passive"))
      (node (ref "R37") (pin "2") (pinfunction "2_2") (pintype "passive"))
      (node (ref "T5") (pin "5") (pinfunction "G_5") (pintype "passive"))
    )
    (net (code "15") (name "J6_D21_A6") (class "Default")
      (node (ref "D8") (pin "3") (pinfunction "CA_3") (pintype "passive"))
      (node (ref "IC1") (pin "37") (pinfunction "(S0:3/T1:1/AIN7)PA07_37") (pintype "bidirectional"))
      (node (ref "R39") (pin "2") (pinfunction "2_2") (pintype "passive"))
      (node (ref "R40") (pin "2") (pinfunction "2_2") (pintype "passive"))
      (node (ref "T4") (pin "2") (pinfunction "G_2") (pintype "passive"))
    )
    (net (code "16") (name "J7_D16_A1") (class "Default")
      (node (ref "D7") (pin "3") (pinfunction "CA_3") (pintype "passive"))
      (node (ref "IC1") (pin "27") (pinfunction "(S5:0/T6:0/AIN10)PB02_27") (pintype "bidirectional"))
      (node (ref "R42") (pin "2") (pinfunction "2_2") (pintype "passive"))
      (node (ref "R43") (pin "2") (pinfunction "2_2") (pintype "passive"))
      (node (ref "T4") (pin "5") (pinfunction "G_5") (pintype "passive"))
    )
    (net (code "17") (name "LED_SWCLK_D36") (class "Default")
      (node (ref "IC1") (pin "25") (pinfunction "(SWCLK/S1:2/T1:0)PA30_25") (pintype "bidirectional"))
      (node (ref "R14") (pin "1") (pinfunction "1_1") (pintype "passive"))
      (node (ref "SWCLK") (pin "1") (pinfunction "P_1") (pintype "passive"))
    )
    (net (code "18") (name "M1A_D7") (class "Default")
      (node (ref "IC1") (pin "14") (pinfunction "(S5:3|3:3/T7:1|0:7)PA21_14") (pintype "bidirectional"))
      (node (ref "IC3") (pin "4") (pinfunction "IN3_4") (pintype "bidirectional"))
    )
    (net (code "19") (name "M1B_D6") (class "Default")
      (node (ref "IC1") (pin "13") (pinfunction "(S5:2|3:2/T7:0|0:6)PA20_13") (pintype "bidirectional"))
      (node (ref "IC3") (pin "5") (pinfunction "IN4_5") (pintype "bidirectional"))
    )
    (net (code "20") (name "M2A_D1") (class "Default")
      (node (ref "IC1") (pin "16") (pinfunction "(SCL/S3:1|5:1/T4:1|0:5)PA23_16") (pintype "bidirectional"))
      (node (ref "IC3") (pin "1") (pinfunction "IN1_1") (pintype "bidirectional"))
    )
    (net (code "21") (name "M2B_D0") (class "Default")
      (node (ref "IC1") (pin "15") (pinfunction "(SDA/S3:0|5:0/T4:0|0:4)PA22_15") (pintype "bidirectional"))
      (node (ref "IC3") (pin "2") (pinfunction "IN2_2") (pintype "bidirectional"))
    )
    (net (code "22") (name "M3A_D3") (class "Default")
      (node (ref "IC1") (pin "41") (pinfunction "(S0:3|2:3/T1:1|0:3/AIN19)PA11_41") (pintype "bidirectional"))
      (node (ref "IC4") (pin "4") (pinfunction "IN3_4") (pintype "bidirectional"))
    )
    (net (code "23") (name "M3B_D2") (class "Default")
      (node (ref "IC1") (pin "40") (pinfunction "(S0:2|2:2/T1:0|0:2/AIN18)PA10_40") (pintype "bidirectional"))
      (node (ref "IC4") (pin "5") (pinfunction "IN4_5") (pintype "bidirectional"))
    )
    (net (code "24") (name "M4A_D5") (class "Default")
      (node (ref "IC1") (pin "44") (pinfunction "(S4:3/T5:1|0:5)PB11_44") (pintype "bidirectional"))
      (node (ref "IC4") (pin "1") (pinfunction "IN1_1") (pintype "bidirectional"))
    )
    (net (code "25") (name "M4B_D4") (class "Default")
      (node (ref "IC1") (pin "43") (pinfunction "(S4:2/T5:0|0:4)PB10_43") (pintype "bidirectional"))
      (node (ref "IC4") (pin "2") (pinfunction "IN2_2") (pintype "bidirectional"))
    )
    (net (code "26") (name "MISO_D10_LV") (class "Default")
      (node (ref "IC1") (pin "12") (pinfunction "(S1:3|3:3/T3:1|0:3)PA19_12") (pintype "bidirectional"))
      (node (ref "R19") (pin "1") (pinfunction "1_1") (pintype "passive"))
    )
    (net (code "27") (name "MISO_HV") (class "Default")
      (node (ref "IC2") (pin "6") (pinfunction "A3_6") (pintype "input"))
      (node (ref "SPI") (pin "3") (pinfunction "3_3") (pintype "passive"))
    )
    (net (code "28") (name "MOSI_D8_LV") (class "Default")
      (node (ref "IC1") (pin "8") (pinfunction "(SDA/S1:0|3:0/T2:0|0:6)PA16_8") (pintype "bidirectional"))
      (node (ref "IC2") (pin "2") (pinfunction "A1_2") (pintype "input"))
    )
    (net (code "29") (name "MOSI_HV") (class "Default")
      (node (ref "IC2") (pin "18") (pinfunction "Y1_18") (pintype "tri_state"))
      (node (ref "SPI") (pin "4") (pinfunction "4_4") (pintype "passive"))
    )
    (net (code "30") (name "Net-(C5-Pad2)") (class "Default")
      (node (ref "C5") (pin "2") (pinfunction "2_2") (pintype "passive"))
      (node (ref "R3") (pin "1") (pinfunction "1_1") (pintype "passive"))
    )
    (net (code "31") (name "Net-(IC1-(XIN32{slash}S1:0{slash}T2:0)PA00)") (class "Default")
      (node (ref "C17") (pin "1") (pinfunction "1_1") (pintype "passive"))
      (node (ref "IC1") (pin "29") (pinfunction "(XIN32/S1:0/T2:0)PA00_29") (pintype "bidirectional"))
      (node (ref "Q1") (pin "2") (pinfunction "2_2") (pintype "passive"))
    )
    (net (code "32") (name "Net-(IC1-(XOUT32{slash}S1:1{slash}T2:1)PA01)") (class "Default")
      (node (ref "C18") (pin "1") (pinfunction "1_1") (pintype "passive"))
      (node (ref "IC1") (pin "30") (pinfunction "(XOUT32/S1:1/T2:1)PA01_30") (pintype "bidirectional"))
      (node (ref "Q1") (pin "1") (pinfunction "1_1") (pintype "passive"))
    )
    (net (code "33") (name "Net-(IC1-5{slash}16{slash}LEDG)") (class "Default")
      (node (ref "IC1") (pin "46") (pinfunction "5/16/LEDG_46") (pintype "bidirectional"))
      (node (ref "R10") (pin "1") (pinfunction "1_1") (pintype "passive"))
    )
    (net (code "34") (name "Net-(IC1-6{slash}18{slash}LEDR)") (class "Default")
      (node (ref "IC1") (pin "47") (pinfunction "6/18/LEDR_47") (pintype "bidirectional"))
      (node (ref "R11") (pin "1") (pinfunction "1_1") (pintype "passive"))
    )
    (net (code "35") (name "Net-(IC2A-Y3)") (class "Default")
      (node (ref "IC2") (pin "14") (pinfunction "Y3_14") (pintype "tri_state"))
      (node (ref "R19") (pin "2") (pinfunction "2_2") (pintype "passive"))
    )
    (net (code "36") (name "Net-(IC2B-Y3)") (class "Default")
      (node (ref "IC2") (pin "5") (pinfunction "Y3_5") (pintype "tri_state"))
      (node (ref "R20") (pin "2") (pinfunction "2_2") (pintype "passive"))
    )
    (net (code "37") (name "Net-(IC3-OUT1)") (class "Default")
      (node (ref "IC3") (pin "10") (pinfunction "OUT1_10") (pintype "passive"))
      (node (ref "M2") (pin "2") (pinfunction "1_2") (pintype "passive"))
    )
    (net (code "38") (name "Net-(IC3-OUT2)") (class "Default")
      (node (ref "IC3") (pin "9") (pinfunction "OUT2_9") (pintype "passive"))
      (node (ref "M2") (pin "1") (pinfunction "2_1") (pintype "passive"))
    )
    (net (code "39") (name "Net-(IC3-OUT3)") (class "Default")
      (node (ref "IC3") (pin "7") (pinfunction "OUT3_7") (pintype "passive"))
      (node (ref "M1") (pin "2") (pinfunction "1_2") (pintype "passive"))
    )
    (net (code "40") (name "Net-(IC3-OUT4)") (class "Default")
      (node (ref "IC3") (pin "6") (pinfunction "OUT4_6") (pintype "passive"))
      (node (ref "M1") (pin "1") (pinfunction "2_1") (pintype "passive"))
    )
    (net (code "41") (name "Net-(IC4-OUT1)") (class "Default")
      (node (ref "IC4") (pin "10") (pinfunction "OUT1_10") (pintype "passive"))
      (node (ref "M4") (pin "2") (pinfunction "1_2") (pintype "passive"))
    )
    (net (code "42") (name "Net-(IC4-OUT2)") (class "Default")
      (node (ref "IC4") (pin "9") (pinfunction "OUT2_9") (pintype "passive"))
      (node (ref "M4") (pin "1") (pinfunction "2_1") (pintype "passive"))
    )
    (net (code "43") (name "Net-(IC4-OUT3)") (class "Default")
      (node (ref "IC4") (pin "7") (pinfunction "OUT3_7") (pintype "passive"))
      (node (ref "M3") (pin "2") (pinfunction "1_2") (pintype "passive"))
    )
    (net (code "44") (name "Net-(IC4-OUT4)") (class "Default")
      (node (ref "IC4") (pin "6") (pinfunction "OUT4_6") (pintype "passive"))
      (node (ref "M3") (pin "1") (pinfunction "2_1") (pintype "passive"))
    )
    (net (code "45") (name "Net-(IC6-BOOST)") (class "Default")
      (node (ref "C4") (pin "2") (pinfunction "2_2") (pintype "passive"))
      (node (ref "IC6") (pin "1") (pinfunction "BOOST_1") (pintype "passive"))
    )
    (net (code "46") (name "Net-(IC6-COMP)") (class "Default")
      (node (ref "IC6") (pin "6") (pinfunction "COMP_6") (pintype "passive"))
      (node (ref "R3") (pin "2") (pinfunction "2_2") (pintype "passive"))
    )
    (net (code "47") (name "Net-(IC6-EN)") (class "Default")
      (node (ref "IC6") (pin "7") (pinfunction "EN_7") (pintype "input"))
      (node (ref "R1") (pin "1") (pinfunction "1_1") (pintype "passive"))
      (node (ref "R2") (pin "2") (pinfunction "2_2") (pintype "passive"))
    )
    (net (code "48") (name "Net-(IC6-FB)") (class "Default")
      (node (ref "IC6") (pin "5") (pinfunction "FB_5") (pintype "passive"))
      (node (ref "R4") (pin "1") (pinfunction "1_1") (pintype "passive"))
      (node (ref "R5") (pin "2") (pinfunction "2_2") (pintype "passive"))
    )
    (net (code "49") (name "Net-(IC6-SS)") (class "Default")
      (node (ref "C3") (pin "2") (pinfunction "2_2") (pintype "passive"))
      (node (ref "IC6") (pin "8") (pinfunction "SS_8") (pintype "passive"))
    )
    (net (code "50") (name "Net-(IC6-SW)") (class "Default")
      (node (ref "C4") (pin "1") (pinfunction "1_1") (pintype "passive"))
      (node (ref "IC6") (pin "3") (pinfunction "SW_3") (pintype "passive"))
      (node (ref "L1") (pin "1") (pinfunction "1_1") (pintype "passive"))
    )
    (net (code "51") (name "Net-(IC6-VIN)") (class "Default")
      (node (ref "C1") (pin "2") (pinfunction "2_2") (pintype "passive"))
      (node (ref "C2") (pin "2") (pinfunction "2_2") (pintype "passive"))
      (node (ref "D1") (pin "C") (pinfunction "C_C") (pintype "passive"))
      (node (ref "D2") (pin "C") (pinfunction "C_C") (pintype "passive"))
      (node (ref "F1") (pin "1") (pinfunction "1_1") (pintype "passive"))
      (node (ref "IC6") (pin "2") (pinfunction "VIN_2") (pintype "power_in"))
      (node (ref "R1") (pin "2") (pinfunction "2_2") (pintype "passive"))
    )
    (net (code "52") (name "Net-(J1-Pad3)") (class "Default")
      (node (ref "J1") (pin "3") (pinfunction "3_3") (pintype "passive"))
      (node (ref "R24") (pin "1") (pinfunction "1_1") (pintype "passive"))
    )
    (net (code "53") (name "Net-(J2-Pad3)") (class "Default")
      (node (ref "J2") (pin "3") (pinfunction "3_3") (pintype "passive"))
      (node (ref "R27") (pin "1") (pinfunction "1_1") (pintype "passive"))
    )
    (net (code "54") (name "Net-(J3-Pad3)") (class "Default")
      (node (ref "J3") (pin "3") (pinfunction "3_3") (pintype "passive"))
      (node (ref "R30") (pin "1") (pinfunction "1_1") (pintype "passive"))
    )
    (net (code "55") (name "Net-(J4-Pad3)") (class "Default")
      (node (ref "J4") (pin "3") (pinfunction "3_3") (pintype "passive"))
      (node (ref "R33") (pin "1") (pinfunction "1_1") (pintype "passive"))
    )
    (net (code "56") (name "Net-(J5-Pad3)") (class "Default")
      (node (ref "J5") (pin "3") (pinfunction "3_3") (pintype "passive"))
      (node (ref "R36") (pin "1") (pinfunction "1_1") (pintype "passive"))
    )
    (net (code "57") (name "Net-(J6-Pad3)") (class "Default")
      (node (ref "J6") (pin "3") (pinfunction "3_3") (pintype "passive"))
      (node (ref "R39") (pin "1") (pinfunction "1_1") (pintype "passive"))
    )
    (net (code "58") (name "Net-(J7-Pad3)") (class "Default")
      (node (ref "J7") (pin "3") (pinfunction "3_3") (pintype "passive"))
      (node (ref "R42") (pin "1") (pinfunction "1_1") (pintype "passive"))
    )
    (net (code "59") (name "Net-(LED1-PadA)") (class "Default")
      (node (ref "LED1") (pin "A") (pinfunction "A_A") (pintype "passive"))
      (node (ref "R26") (pin "1") (pinfunction "1_1") (pintype "passive"))
    )
    (net (code "60") (name "Net-(LED2-PadA)") (class "Default")
      (node (ref "LED2") (pin "A") (pinfunction "A_A") (pintype "passive"))
      (node (ref "R29") (pin "1") (pinfunction "1_1") (pintype "passive"))
    )
    (net (code "61") (name "Net-(LED3-PadA)") (class "Default")
      (node (ref "LED3") (pin "A") (pinfunction "A_A") (pintype "passive"))
      (node (ref "R32") (pin "1") (pinfunction "1_1") (pintype "passive"))
    )
    (net (code "62") (name "Net-(LED4-PadA)") (class "Default")
      (node (ref "LED4") (pin "A") (pinfunction "A_A") (pintype "passive"))
      (node (ref "R35") (pin "1") (pinfunction "1_1") (pintype "passive"))
    )
    (net (code "63") (name "Net-(LED5-PadA)") (class "Default")
      (node (ref "LED5") (pin "A") (pinfunction "A_A") (pintype "passive"))
      (node (ref "R38") (pin "1") (pinfunction "1_1") (pintype "passive"))
    )
    (net (code "64") (name "Net-(LED6-PadA)") (class "Default")
      (node (ref "LED6") (pin "A") (pinfunction "A_A") (pintype "passive"))
      (node (ref "R41") (pin "1") (pinfunction "1_1") (pintype "passive"))
    )
    (net (code "65") (name "Net-(LED7-PadA)") (class "Default")
      (node (ref "LED7") (pin "A") (pinfunction "A_A") (pintype "passive"))
      (node (ref "R44") (pin "1") (pinfunction "1_1") (pintype "passive"))
    )
    (net (code "66") (name "Net-(LED8-PadA)") (class "Default")
      (node (ref "LED8") (pin "A") (pinfunction "A_A") (pintype "passive"))
      (node (ref "R22") (pin "2") (pinfunction "2_2") (pintype "passive"))
    )
    (net (code "67") (name "Net-(LED9-PadA)") (class "Default")
      (node (ref "LED9") (pin "A") (pinfunction "A_A") (pintype "passive"))
      (node (ref "R14") (pin "2") (pinfunction "2_2") (pintype "passive"))
    )
    (net (code "68") (name "Net-(LED16-PadA)") (class "Default")
      (node (ref "LED16") (pin "A") (pinfunction "A_A") (pintype "passive"))
      (node (ref "R10") (pin "2") (pinfunction "2_2") (pintype "passive"))
    )
    (net (code "69") (name "Net-(LED18-PadA)") (class "Default")
      (node (ref "LED18") (pin "A") (pinfunction "A_A") (pintype "passive"))
      (node (ref "R11") (pin "2") (pinfunction "2_2") (pintype "passive"))
    )
    (net (code "70") (name "Net-(R6-Pad2)") (class "Default")
      (node (ref "R6") (pin "2") (pinfunction "2_2") (pintype "passive"))
      (node (ref "USB") (pin "SHLD1") (pinfunction "SHIELD_SHLD1") (pintype "passive"))
      (node (ref "USB") (pin "SHLD2") (pinfunction "SHIELD_SHLD2") (pintype "passive"))
      (node (ref "USB") (pin "SHLD3") (pinfunction "SHIELD_SHLD3") (pintype "passive"))
    )
    (net (code "71") (name "Net-(R45-Pad2)") (class "Default")
      (node (ref "R45") (pin "2") (pinfunction "2_2") (pintype "passive"))
      (node (ref "RESET") (pin "2") (pinfunction "S1_2") (pintype "passive"))
      (node (ref "RESET") (pin "3") (pinfunction "S1_3") (pintype "passive"))
    )
    (net (code "72") (name "Net-(S1-2)") (class "Default")
      (node (ref "D6") (pin "A") (pinfunction "A_A") (pintype "passive"))
      (node (ref "S1") (pin "1") (pinfunction "2_1") (pintype "passive"))
      (node (ref "T2") (pin "3") (pinfunction "D_3") (pintype "passive"))
    )
    (net (code "73") (name "Net-(T1-D)") (class "Default")
      (node (ref "F2") (pin "2") (pinfunction "2_2") (pintype "passive"))
      (node (ref "T1") (pin "3") (pinfunction "D_3") (pintype "passive"))
    )
    (net (code "74") (name "Net-(T1-G)") (class "Default")
      (node (ref "R7") (pin "2") (pinfunction "2_2") (pintype "passive"))
      (node (ref "R8") (pin "1") (pinfunction "1_1") (pintype "passive"))
      (node (ref "T1") (pin "1") (pinfunction "G_1") (pintype "passive"))
    )
    (net (code "75") (name "Net-(T2-G)") (class "Default")
      (node (ref "R21") (pin "2") (pinfunction "2_2") (pintype "passive"))
      (node (ref "R22") (pin "1") (pinfunction "1_1") (pintype "passive"))
      (node (ref "R23") (pin "2") (pinfunction "2_2") (pintype "passive"))
      (node (ref "T2") (pin "1") (pinfunction "G_1") (pintype "passive"))
    )
    (net (code "76") (name "Net-(T4A-D)") (class "Default")
      (node (ref "LED6") (pin "C") (pinfunction "C_C") (pintype "passive"))
      (node (ref "T4") (pin "6") (pinfunction "D_6") (pintype "passive"))
    )
    (net (code "77") (name "Net-(T4B-D)") (class "Default")
      (node (ref "LED7") (pin "C") (pinfunction "C_C") (pintype "passive"))
      (node (ref "T4") (pin "3") (pinfunction "D_3") (pintype "passive"))
    )
    (net (code "78") (name "Net-(T5A-D)") (class "Default")
      (node (ref "LED4") (pin "C") (pinfunction "C_C") (pintype "passive"))
      (node (ref "T5") (pin "6") (pinfunction "D_6") (pintype "passive"))
    )
    (net (code "79") (name "Net-(T5B-D)") (class "Default")
      (node (ref "LED5") (pin "C") (pinfunction "C_C") (pintype "passive"))
      (node (ref "T5") (pin "3") (pinfunction "D_3") (pintype "passive"))
    )
    (net (code "80") (name "Net-(T6A-D)") (class "Default")
      (node (ref "LED2") (pin "C") (pinfunction "C_C") (pintype "passive"))
      (node (ref "T6") (pin "6") (pinfunction "D_6") (pintype "passive"))
    )
    (net (code "81") (name "Net-(T6B-D)") (class "Default")
      (node (ref "LED3") (pin "C") (pinfunction "C_C") (pintype "passive"))
      (node (ref "T6") (pin "3") (pinfunction "D_3") (pintype "passive"))
    )
    (net (code "82") (name "Net-(T7A-D)") (class "Default")
      (node (ref "LED1") (pin "C") (pinfunction "C_C") (pintype "passive"))
      (node (ref "T7") (pin "6") (pinfunction "D_6") (pintype "passive"))
    )
    (net (code "83") (name "RST") (class "Default")
      (node (ref "C14") (pin "2") (pinfunction "2_2") (pintype "passive"))
      (node (ref "IC1") (pin "24") (pinfunction "~{RESET}_24") (pintype "input"))
      (node (ref "R45") (pin "1") (pinfunction "1_1") (pintype "passive"))
      (node (ref "R9") (pin "2") (pinfunction "2_2") (pintype "passive"))
      (node (ref "RST") (pin "1") (pinfunction "P_1") (pintype "passive"))
    )
    (net (code "84") (name "RX_D13_LV") (class "Default")
      (node (ref "IC1") (pin "23") (pinfunction "(S5:3/T7:1)PB23_23") (pintype "bidirectional"))
      (node (ref "R20") (pin "1") (pinfunction "1_1") (pintype "passive"))
    )
    (net (code "85") (name "RX_HV") (class "Default")
      (node (ref "IC2") (pin "15") (pinfunction "A3_15") (pintype "input"))
      (node (ref "UART") (pin "3") (pinfunction "3_3") (pintype "passive"))
    )
    (net (code "86") (name "S1_SWDIO_D37") (class "Default")
      (node (ref "IC1") (pin "26") (pinfunction "(SWDIO/S1:3/T1:1)PA31_26") (pintype "bidirectional"))
      (node (ref "R21") (pin "1") (pinfunction "1_1") (pintype "passive"))
      (node (ref "SWDIO") (pin "1") (pinfunction "P_1") (pintype "passive"))
    )
    (net (code "87") (name "SCK_D9_LV") (class "Default")
      (node (ref "IC1") (pin "9") (pinfunction "(SCL/S1:1|3:1/T2:1|0:7)PA17_9") (pintype "bidirectional"))
      (node (ref "IC2") (pin "4") (pinfunction "A2_4") (pintype "input"))
    )
    (net (code "88") (name "SCK_HV") (class "Default")
      (node (ref "IC2") (pin "16") (pinfunction "Y2_16") (pintype "tri_state"))
      (node (ref "SPI") (pin "5") (pinfunction "5_5") (pintype "passive"))
    )
    (net (code "89") (name "SCL_D12_LV") (class "Default")
      (node (ref "IC1") (pin "39") (pinfunction "(SCL/S0:1|2:1/T0:1|1:3/AIN17)PA09_39") (pintype "bidirectional"))
      (node (ref "R15") (pin "1") (pinfunction "1_1") (pintype "passive"))
      (node (ref "T3") (pin "4") (pinfunction "S_4") (pintype "passive"))
    )
    (net (code "90") (name "SDA_D11_LV") (class "Default")
      (node (ref "IC1") (pin "38") (pinfunction "(SDA/S0:0|2:0/T0:0|1:2/AIN16)PA08_38") (pintype "bidirectional"))
      (node (ref "R17") (pin "1") (pinfunction "1_1") (pintype "passive"))
      (node (ref "T3") (pin "1") (pinfunction "S_1") (pintype "passive"))
    )
    (net (code "91") (name "TX_D14_LV") (class "Default")
      (node (ref "IC1") (pin "22") (pinfunction "(S5:2/T7:0)PB22_22") (pintype "bidirectional"))
      (node (ref "IC2") (pin "13") (pinfunction "A2_13") (pintype "input"))
    )
    (net (code "92") (name "TX_HV") (class "Default")
      (node (ref "IC2") (pin "7") (pinfunction "Y2_7") (pintype "tri_state"))
      (node (ref "UART") (pin "4") (pinfunction "4_4") (pintype "passive"))
    )
    (net (code "93") (name "USB_N") (class "Default")
      (node (ref "D-") (pin "1") (pinfunction "P_1") (pintype "passive"))
      (node (ref "D14") (pin "1") (pinfunction "C1_1") (pintype "passive"))
      (node (ref "IC1") (pin "18") (pinfunction "(USB_DM/S3:2|5:2/T5:0|1:2)PA24_18") (pintype "bidirectional"))
      (node (ref "USB") (pin "D-") (pinfunction "D-_D-") (pintype "bidirectional"))
    )
    (net (code "94") (name "USB_P") (class "Default")
      (node (ref "D+") (pin "1") (pinfunction "P_1") (pintype "passive"))
      (node (ref "D14") (pin "2") (pinfunction "C2_2") (pintype "passive"))
      (node (ref "IC1") (pin "19") (pinfunction "(USB_DP/S3:3|5:3/T5:1|1:3)PA25_19") (pintype "bidirectional"))
      (node (ref "USB") (pin "D+") (pinfunction "D+_D+") (pintype "bidirectional"))
    )
    (net (code "95") (name "V+") (class "Default")
      (node (ref "C19") (pin "1") (pinfunction "1_1") (pintype "passive"))
      (node (ref "C20") (pin "1") (pinfunction "1_1") (pintype "passive"))
      (node (ref "D6") (pin "C") (pinfunction "C_C") (pintype "passive"))
      (node (ref "F1") (pin "2") (pinfunction "2_2") (pintype "passive"))
      (node (ref "IC3") (pin "3") (pinfunction "VBB_3") (pintype "power_in"))
      (node (ref "IC4") (pin "3") (pinfunction "VBB_3") (pintype "power_in"))
      (node (ref "R12") (pin "1") (pinfunction "1_1") (pintype "passive"))
      (node (ref "S1") (pin "2") (pinfunction "1_2") (pintype "passive"))
    )
    (net (code "96") (name "VBUS") (class "Default")
      (node (ref "C10") (pin "2") (pinfunction "2_2") (pintype "passive"))
      (node (ref "F2") (pin "1") (pinfunction "1_1") (pintype "passive"))
      (node (ref "USB") (pin "VBUS") (pinfunction "VBUS_VBUS") (pintype "power_in"))
      (node (ref "VBUS") (pin "1") (pinfunction "P_1") (pintype "passive"))
    )
    (net (code "97") (name "VIN") (class "Default")
      (node (ref "D1") (pin "A") (pinfunction "A_A") (pintype "passive"))
      (node (ref "POWER") (pin "2") (pinfunction "1_2") (pintype "passive"))
      (node (ref "R8") (pin "2") (pinfunction "2_2") (pintype "passive"))
    )
    (net (code "98") (name "unconnected-(IC1-1{slash}RTC-Pad5)") (class "Default")
      (node (ref "IC1") (pin "5") (pinfunction "1/RTC_5") (pintype "bidirectional"))
    )
    (net (code "99") (name "unconnected-(IC1-3{slash}NC-Pad6)") (class "Default")
      (node (ref "IC1") (pin "6") (pinfunction "3/NC_6") (pintype "bidirectional"))
    )
    (net (code "100") (name "unconnected-(IC1-4{slash}15-Pad45)") (class "Default")
      (node (ref "IC1") (pin "45") (pinfunction "4/15_45") (pintype "bidirectional"))
    )
    (net (code "101") (name "unconnected-(IC1-CHIP_EN-Pad4)") (class "Default")
      (node (ref "IC1") (pin "4") (pinfunction "CHIP_EN_4") (pintype "input"))
    )
    (net (code "102") (name "unconnected-(IC1-RXD-Pad3)") (class "Default")
      (node (ref "IC1") (pin "3") (pinfunction "RXD_3") (pintype "input"))
    )
    (net (code "103") (name "unconnected-(IC1-SCL-Pad48)") (class "Default")
      (node (ref "IC1") (pin "48") (pinfunction "SCL_48") (pintype "bidirectional"))
    )
    (net (code "104") (name "unconnected-(IC1-SDA-Pad49)") (class "Default")
      (node (ref "IC1") (pin "49") (pinfunction "SDA_49") (pintype "bidirectional"))
    )
    (net (code "105") (name "unconnected-(IC1-TXD-Pad2)") (class "Default")
      (node (ref "IC1") (pin "2") (pinfunction "TXD_2") (pintype "output"))
    )
    (net (code "106") (name "unconnected-(IC1-W~{RESET}-Pad50)") (class "Default")
      (node (ref "IC1") (pin "50") (pinfunction "W~{RESET}_50") (pintype "input"))
    )
    (net (code "107") (name "unconnected-(IC2A-Y4-Pad12)") (class "Default")
      (node (ref "IC2") (pin "12") (pinfunction "Y4_12") (pintype "tri_state"))
    )
    (net (code "108") (name "unconnected-(IC2B-Y4-Pad3)") (class "Default")
      (node (ref "IC2") (pin "3") (pinfunction "Y4_3") (pintype "tri_state"))
    )
    (net (code "109") (name "unconnected-(USB-PadID)") (class "Default")
      (node (ref "USB") (pin "ID") (pinfunction "ID_ID") (pintype "bidirectional"))
    )
  )
)
